# main.net
KiCad netlist of a schematic drawn in Altium Designer
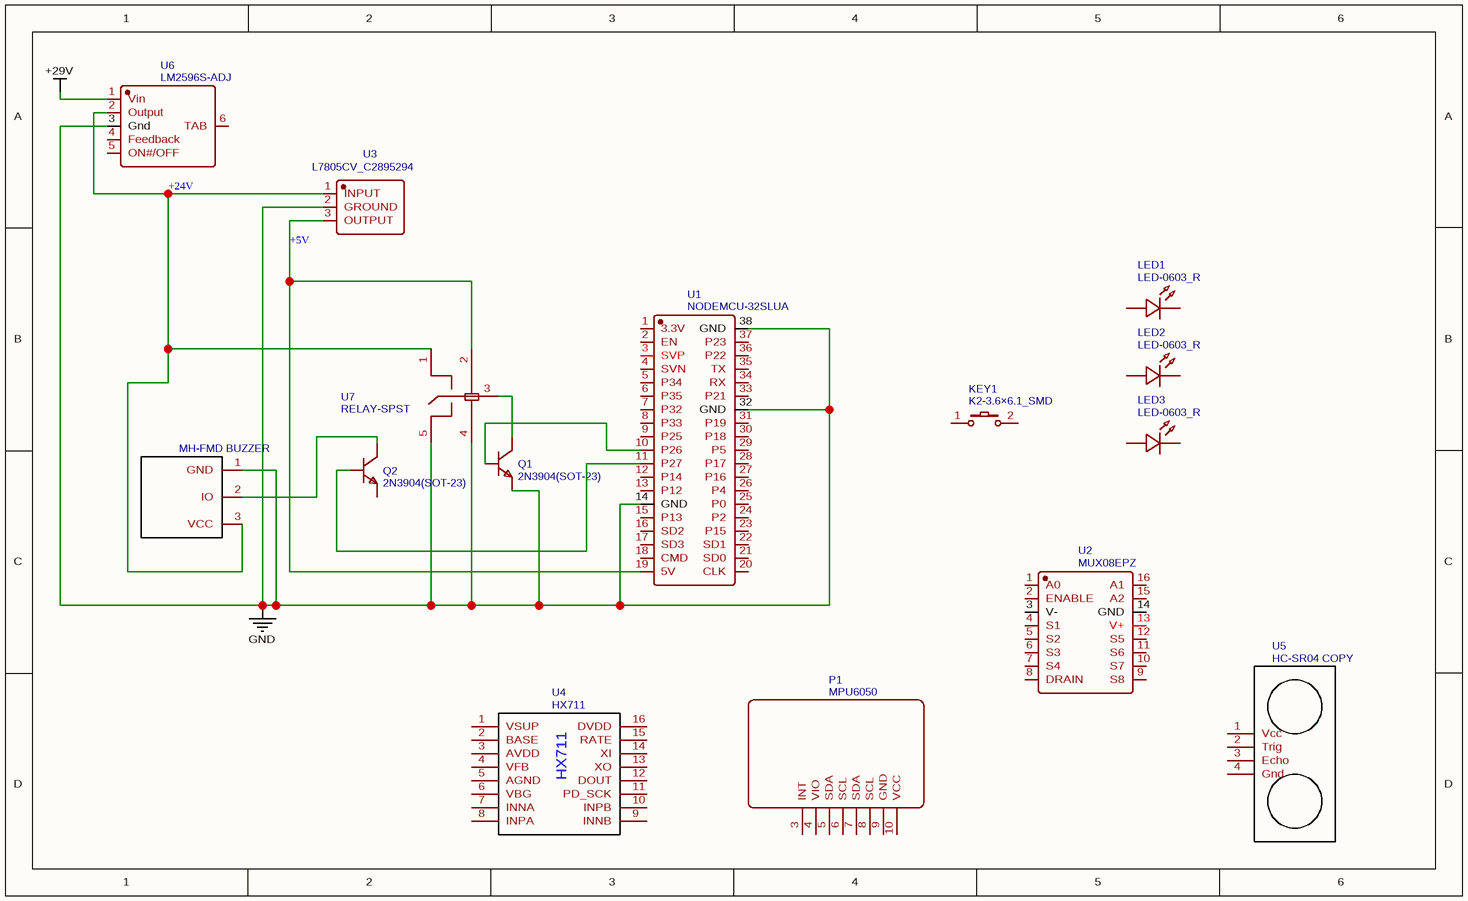
[diagram p0: main.schdoc]

(export (version "E")
  (design (tool "Eeschema 10.0.6"))
  (components
    (comp (ref "GND")
      (value "MH-FMD BUZZER")
      (fields (field (name "BOM_SUPPLIER PART") "MH-FMD") (field (name "CONTRIBUTOR") "toms56"))
      (libsource (lib "altium-import") (part "root_0_MH-FMD BUZZER_"))
    )
    (comp (ref "KEY1")
      (value "K2-3.6×6.1_SMD")
      (fields
        (field (name "BOM_SUPPLIER PART") "C118141")
        (field (name "BOM_MANUFACTURER PART") "K2-1107ST-A4SW-06")
        (field (name "CONTRIBUTOR") "LCEDA_Lib")
      )
      (libsource (lib "altium-import") (part "root_0_K2-3.6×6.1_SMD_"))
    )
    (comp (ref "LED1")
      (value "LED-0603_R")
      (fields
        (field (name "BOM_MANUFACTURER PART") "19-217/R6C-AL1M2VY/3T")
        (field (name "BOM_SUPPLIER PART") "C72044")
        (field (name "CONTRIBUTOR") "LCEDA_01")
      )
      (libsource (lib "altium-import") (part "root_0_LED-0603_R_"))
    )
    (comp (ref "LED2")
      (value "LED-0603_R")
      (fields
        (field (name "BOM_MANUFACTURER PART") "19-217/R6C-AL1M2VY/3T")
        (field (name "BOM_SUPPLIER PART") "C72044")
        (field (name "CONTRIBUTOR") "LCEDA_01")
      )
      (libsource (lib "altium-import") (part "root_0_LED-0603_R_"))
    )
    (comp (ref "LED3")
      (value "LED-0603_R")
      (fields
        (field (name "BOM_MANUFACTURER PART") "19-217/R6C-AL1M2VY/3T")
        (field (name "BOM_SUPPLIER PART") "C72044")
        (field (name "CONTRIBUTOR") "LCEDA_01")
      )
      (libsource (lib "altium-import") (part "root_0_LED-0603_R_"))
    )
    (comp (ref "P1")
      (value "MPU6050")
      (fields (field (name "CONTRIBUTOR") "AmrKhaled123"))
      (libsource (lib "altium-import") (part "root_0_MPU6050_"))
    )
    (comp (ref "Q1")
      (value "2N3904(SOT-23)")
      (fields
        (field (name "BOM_MANUFACTURER PART") "2n3904S-RTK/PS")
        (field (name "BOM_SUPPLIER PART") "C18536")
        (field (name "CONTRIBUTOR") "LCEDA_Lib")
      )
      (libsource (lib "altium-import") (part "root_0_2N3904(SOT-23)_"))
    )
    (comp (ref "Q2")
      (value "2N3904(SOT-23)")
      (fields
        (field (name "BOM_MANUFACTURER PART") "2n3904S-RTK/PS")
        (field (name "BOM_SUPPLIER PART") "C18536")
        (field (name "CONTRIBUTOR") "LCEDA_Lib")
      )
      (libsource (lib "altium-import") (part "root_0_2N3904(SOT-23)_"))
    )
    (comp (ref "U1")
      (value "NODEMCU-32SLUA")
      (fields
        (field (name "BOM_SUPPLIER PART") "C111436")
        (field (name "BOM_MANUFACTURER PART") "NodeMCU-32SLua")
        (field (name "CONTRIBUTOR") "lcsc")
      )
      (libsource (lib "altium-import") (part "root_0_NODEMCU-32SLUA_"))
    )
    (comp (ref "U2")
      (value "MUX08EPZ")
      (fields (field (name "BOM_SUPPLIER PART") "C690856") (field (name "CONTRIBUTOR") "LCSC"))
      (libsource (lib "altium-import") (part "root_0_MUX08EPZ_"))
    )
    (comp (ref "U3")
      (value "L7805CV_C2895294")
      (fields
        (field (name "BOM_SUPPLIER PART") "C2895294")
        (field (name "BOM_MANUFACTURER PART") "L7805CV带散热器")
        (field (name "CONTRIBUTOR") "LCSC")
      )
      (libsource (lib "altium-import") (part "root_0_L7805CV_C2895294_"))
    )
    (comp (ref "U4")
      (value "HX711")
      (fields (field (name "BOM_SUPPLIER PART") "C43656"))
      (libsource (lib "altium-import") (part "root_0_HX711_"))
    )
    (comp (ref "U5")
      (value "HC-SR04 COPY")
      (fields (field (name "CONTRIBUTOR") "allvex"))
      (libsource (lib "altium-import") (part "root_0_HC-SR04 COPY_"))
    )
    (comp (ref "U6")
      (value "LM2596S-ADJ")
      (fields (field (name "BOM_SUPPLIER PART") "C347423") (field (name "CONTRIBUTOR") "LCSC"))
      (libsource (lib "altium-import") (part "root_0_LM2596S-ADJ_"))
    )
    (comp (ref "U7")
      (value "RELAY-SPST")
      (fields
        (field (name "BOM_SUPPLIER PART") "C2941249")
        (field (name "BOM_MANUFACTURER PART") "Relay-SPST")
        (field (name "CONTRIBUTOR") "LCSC")
      )
      (libsource (lib "altium-import") (part "root_0_RELAY-SPST_"))
    )
  )
  (nets
    (net (code "1") (name "+29V") (class "Default")
      (node (ref "U6") (pin "1") (pinfunction "Vin_1") (pintype "passive"))
    )
    (net (code "2") (name "/+5V") (class "Default")
      (node (ref "U1") (pin "19") (pinfunction "5V_19") (pintype "passive"))
      (node (ref "U3") (pin "3") (pinfunction "OUTPUT_3") (pintype "passive"))
      (node (ref "U7") (pin "2") (pinfunction "2_2") (pintype "passive"))
    )
    (net (code "3") (name "/+24V") (class "Default")
      (node (ref "GND") (pin "3") (pinfunction "VCC_3") (pintype "passive"))
      (node (ref "U3") (pin "1") (pinfunction "INPUT_1") (pintype "passive"))
      (node (ref "U6") (pin "2") (pinfunction "Output_2") (pintype "passive"))
      (node (ref "U7") (pin "1") (pinfunction "1_1") (pintype "passive"))
    )
    (net (code "4") (name "GND") (class "Default")
      (node (ref "GND") (pin "1") (pinfunction "GND_1") (pintype "passive"))
      (node (ref "Q1") (pin "1") (pinfunction "E_1") (pintype "passive"))
      (node (ref "U1") (pin "14") (pinfunction "GND_14") (pintype "passive"))
      (node (ref "U1") (pin "32") (pinfunction "GND_32") (pintype "passive"))
      (node (ref "U1") (pin "38") (pinfunction "GND_38") (pintype "passive"))
      (node (ref "U3") (pin "2") (pinfunction "GROUND_2") (pintype "passive"))
      (node (ref "U6") (pin "3") (pinfunction "Gnd_3") (pintype "passive"))
      (node (ref "U7") (pin "4") (pinfunction "4_4") (pintype "passive"))
      (node (ref "U7") (pin "5") (pinfunction "5_5") (pintype "passive"))
    )
    (net (code "5") (name "Net-(GND-IO)") (class "Default")
      (node (ref "GND") (pin "2") (pinfunction "IO_2") (pintype "passive"))
      (node (ref "Q2") (pin "3") (pinfunction "C_3") (pintype "passive"))
    )
    (net (code "6") (name "Net-(Q1-B)") (class "Default")
      (node (ref "Q1") (pin "2") (pinfunction "B_2") (pintype "passive"))
      (node (ref "U1") (pin "10") (pinfunction "P26_10") (pintype "passive"))
    )
    (net (code "7") (name "Net-(Q1-C)") (class "Default")
      (node (ref "Q1") (pin "3") (pinfunction "C_3") (pintype "passive"))
      (node (ref "U7") (pin "3") (pinfunction "3_3") (pintype "passive"))
    )
    (net (code "8") (name "Net-(Q2-B)") (class "Default")
      (node (ref "Q2") (pin "2") (pinfunction "B_2") (pintype "passive"))
      (node (ref "U1") (pin "11") (pinfunction "P27_11") (pintype "passive"))
    )
    (net (code "9") (name "unconnected-(KEY1-Pad1)") (class "Default")
      (node (ref "KEY1") (pin "1") (pinfunction "1_1") (pintype "passive"))
    )
    (net (code "10") (name "unconnected-(KEY1-Pad2)") (class "Default")
      (node (ref "KEY1") (pin "2") (pinfunction "2_2") (pintype "passive"))
    )
    (net (code "11") (name "unconnected-(LED1-Pad1)") (class "Default")
      (node (ref "LED1") (pin "1") (pinfunction "1_1") (pintype "passive"))
    )
    (net (code "12") (name "unconnected-(LED1-Pad2)") (class "Default")
      (node (ref "LED1") (pin "2") (pinfunction "2_2") (pintype "passive"))
    )
    (net (code "13") (name "unconnected-(LED2-Pad1)") (class "Default")
      (node (ref "LED2") (pin "1") (pinfunction "1_1") (pintype "passive"))
    )
    (net (code "14") (name "unconnected-(LED2-Pad2)") (class "Default")
      (node (ref "LED2") (pin "2") (pinfunction "2_2") (pintype "passive"))
    )
    (net (code "15") (name "unconnected-(LED3-Pad1)") (class "Default")
      (node (ref "LED3") (pin "1") (pinfunction "1_1") (pintype "passive"))
    )
    (net (code "16") (name "unconnected-(LED3-Pad2)") (class "Default")
      (node (ref "LED3") (pin "2") (pinfunction "2_2") (pintype "passive"))
    )
    (net (code "17") (name "unconnected-(P1-GND-Pad9)") (class "Default")
      (node (ref "P1") (pin "9") (pinfunction "GND_9") (pintype "passive"))
    )
    (net (code "18") (name "unconnected-(P1-INT-Pad3)") (class "Default")
      (node (ref "P1") (pin "3") (pinfunction "INT_3") (pintype "passive"))
    )
    (net (code "19") (name "unconnected-(P1-SCL-Pad6)") (class "Default")
      (node (ref "P1") (pin "6") (pinfunction "SCL_6") (pintype "passive"))
    )
    (net (code "20") (name "unconnected-(P1-SCL-Pad8)") (class "Default")
      (node (ref "P1") (pin "8") (pinfunction "SCL_8") (pintype "passive"))
    )
    (net (code "21") (name "unconnected-(P1-SDA-Pad5)") (class "Default")
      (node (ref "P1") (pin "5") (pinfunction "SDA_5") (pintype "passive"))
    )
    (net (code "22") (name "unconnected-(P1-SDA-Pad7)") (class "Default")
      (node (ref "P1") (pin "7") (pinfunction "SDA_7") (pintype "passive"))
    )
    (net (code "23") (name "unconnected-(P1-VCC-Pad10)") (class "Default")
      (node (ref "P1") (pin "10") (pinfunction "VCC_10") (pintype "passive"))
    )
    (net (code "24") (name "unconnected-(P1-VIO-Pad4)") (class "Default")
      (node (ref "P1") (pin "4") (pinfunction "VIO_4") (pintype "passive"))
    )
    (net (code "25") (name "unconnected-(Q2-E-Pad1)") (class "Default")
      (node (ref "Q2") (pin "1") (pinfunction "E_1") (pintype "passive"))
    )
    (net (code "26") (name "unconnected-(U1-3.3V-Pad1)") (class "Default")
      (node (ref "U1") (pin "1") (pinfunction "3.3V_1") (pintype "passive"))
    )
    (net (code "27") (name "unconnected-(U1-CLK-Pad20)") (class "Default")
      (node (ref "U1") (pin "20") (pinfunction "CLK_20") (pintype "passive"))
    )
    (net (code "28") (name "unconnected-(U1-CMD-Pad18)") (class "Default")
      (node (ref "U1") (pin "18") (pinfunction "CMD_18") (pintype "passive"))
    )
    (net (code "29") (name "unconnected-(U1-EN-Pad2)") (class "Default")
      (node (ref "U1") (pin "2") (pinfunction "EN_2") (pintype "passive"))
    )
    (net (code "30") (name "unconnected-(U1-P0-Pad25)") (class "Default")
      (node (ref "U1") (pin "25") (pinfunction "P0_25") (pintype "passive"))
    )
    (net (code "31") (name "unconnected-(U1-P2-Pad24)") (class "Default")
      (node (ref "U1") (pin "24") (pinfunction "P2_24") (pintype "passive"))
    )
    (net (code "32") (name "unconnected-(U1-P4-Pad26)") (class "Default")
      (node (ref "U1") (pin "26") (pinfunction "P4_26") (pintype "passive"))
    )
    (net (code "33") (name "unconnected-(U1-P5-Pad29)") (class "Default")
      (node (ref "U1") (pin "29") (pinfunction "P5_29") (pintype "passive"))
    )
    (net (code "34") (name "unconnected-(U1-P12-Pad13)") (class "Default")
      (node (ref "U1") (pin "13") (pinfunction "P12_13") (pintype "passive"))
    )
    (net (code "35") (name "unconnected-(U1-P13-Pad15)") (class "Default")
      (node (ref "U1") (pin "15") (pinfunction "P13_15") (pintype "passive"))
    )
    (net (code "36") (name "unconnected-(U1-P14-Pad12)") (class "Default")
      (node (ref "U1") (pin "12") (pinfunction "P14_12") (pintype "passive"))
    )
    (net (code "37") (name "unconnected-(U1-P15-Pad23)") (class "Default")
      (node (ref "U1") (pin "23") (pinfunction "P15_23") (pintype "passive"))
    )
    (net (code "38") (name "unconnected-(U1-P16-Pad27)") (class "Default")
      (node (ref "U1") (pin "27") (pinfunction "P16_27") (pintype "passive"))
    )
    (net (code "39") (name "unconnected-(U1-P17-Pad28)") (class "Default")
      (node (ref "U1") (pin "28") (pinfunction "P17_28") (pintype "passive"))
    )
    (net (code "40") (name "unconnected-(U1-P18-Pad30)") (class "Default")
      (node (ref "U1") (pin "30") (pinfunction "P18_30") (pintype "passive"))
    )
    (net (code "41") (name "unconnected-(U1-P19-Pad31)") (class "Default")
      (node (ref "U1") (pin "31") (pinfunction "P19_31") (pintype "passive"))
    )
    (net (code "42") (name "unconnected-(U1-P21-Pad33)") (class "Default")
      (node (ref "U1") (pin "33") (pinfunction "P21_33") (pintype "passive"))
    )
    (net (code "43") (name "unconnected-(U1-P22-Pad36)") (class "Default")
      (node (ref "U1") (pin "36") (pinfunction "P22_36") (pintype "passive"))
    )
    (net (code "44") (name "unconnected-(U1-P23-Pad37)") (class "Default")
      (node (ref "U1") (pin "37") (pinfunction "P23_37") (pintype "passive"))
    )
    (net (code "45") (name "unconnected-(U1-P25-Pad9)") (class "Default")
      (node (ref "U1") (pin "9") (pinfunction "P25_9") (pintype "passive"))
    )
    (net (code "46") (name "unconnected-(U1-P32-Pad7)") (class "Default")
      (node (ref "U1") (pin "7") (pinfunction "P32_7") (pintype "passive"))
    )
    (net (code "47") (name "unconnected-(U1-P33-Pad8)") (class "Default")
      (node (ref "U1") (pin "8") (pinfunction "P33_8") (pintype "passive"))
    )
    (net (code "48") (name "unconnected-(U1-P34-Pad5)") (class "Default")
      (node (ref "U1") (pin "5") (pinfunction "P34_5") (pintype "passive"))
    )
    (net (code "49") (name "unconnected-(U1-P35-Pad6)") (class "Default")
      (node (ref "U1") (pin "6") (pinfunction "P35_6") (pintype "passive"))
    )
    (net (code "50") (name "unconnected-(U1-RX-Pad34)") (class "Default")
      (node (ref "U1") (pin "34") (pinfunction "RX_34") (pintype "passive"))
    )
    (net (code "51") (name "unconnected-(U1-SD0-Pad21)") (class "Default")
      (node (ref "U1") (pin "21") (pinfunction "SD0_21") (pintype "passive"))
    )
    (net (code "52") (name "unconnected-(U1-SD1-Pad22)") (class "Default")
      (node (ref "U1") (pin "22") (pinfunction "SD1_22") (pintype "passive"))
    )
    (net (code "53") (name "unconnected-(U1-SD2-Pad16)") (class "Default")
      (node (ref "U1") (pin "16") (pinfunction "SD2_16") (pintype "passive"))
    )
    (net (code "54") (name "unconnected-(U1-SD3-Pad17)") (class "Default")
      (node (ref "U1") (pin "17") (pinfunction "SD3_17") (pintype "passive"))
    )
    (net (code "55") (name "unconnected-(U1-SVN-Pad4)") (class "Default")
      (node (ref "U1") (pin "4") (pinfunction "SVN_4") (pintype "passive"))
    )
    (net (code "56") (name "unconnected-(U1-SVP-Pad3)") (class "Default")
      (node (ref "U1") (pin "3") (pinfunction "SVP_3") (pintype "passive"))
    )
    (net (code "57") (name "unconnected-(U1-TX-Pad35)") (class "Default")
      (node (ref "U1") (pin "35") (pinfunction "TX_35") (pintype "passive"))
    )
    (net (code "58") (name "unconnected-(U2-A0-Pad1)") (class "Default")
      (node (ref "U2") (pin "1") (pinfunction "A0_1") (pintype "passive"))
    )
    (net (code "59") (name "unconnected-(U2-A1-Pad16)") (class "Default")
      (node (ref "U2") (pin "16") (pinfunction "A1_16") (pintype "passive"))
    )
    (net (code "60") (name "unconnected-(U2-A2-Pad15)") (class "Default")
      (node (ref "U2") (pin "15") (pinfunction "A2_15") (pintype "passive"))
    )
    (net (code "61") (name "unconnected-(U2-DRAIN-Pad8)") (class "Default")
      (node (ref "U2") (pin "8") (pinfunction "DRAIN_8") (pintype "passive"))
    )
    (net (code "62") (name "unconnected-(U2-ENABLE-Pad2)") (class "Default")
      (node (ref "U2") (pin "2") (pinfunction "ENABLE_2") (pintype "passive"))
    )
    (net (code "63") (name "unconnected-(U2-GND-Pad14)") (class "Default")
      (node (ref "U2") (pin "14") (pinfunction "GND_14") (pintype "passive"))
    )
    (net (code "64") (name "unconnected-(U2-S1-Pad4)") (class "Default")
      (node (ref "U2") (pin "4") (pinfunction "S1_4") (pintype "passive"))
    )
    (net (code "65") (name "unconnected-(U2-S2-Pad5)") (class "Default")
      (node (ref "U2") (pin "5") (pinfunction "S2_5") (pintype "passive"))
    )
    (net (code "66") (name "unconnected-(U2-S3-Pad6)") (class "Default")
      (node (ref "U2") (pin "6") (pinfunction "S3_6") (pintype "passive"))
    )
    (net (code "67") (name "unconnected-(U2-S4-Pad7)") (class "Default")
      (node (ref "U2") (pin "7") (pinfunction "S4_7") (pintype "passive"))
    )
    (net (code "68") (name "unconnected-(U2-S5-Pad12)") (class "Default")
      (node (ref "U2") (pin "12") (pinfunction "S5_12") (pintype "passive"))
    )
    (net (code "69") (name "unconnected-(U2-S6-Pad11)") (class "Default")
      (node (ref "U2") (pin "11") (pinfunction "S6_11") (pintype "passive"))
    )
    (net (code "70") (name "unconnected-(U2-S7-Pad10)") (class "Default")
      (node (ref "U2") (pin "10") (pinfunction "S7_10") (pintype "passive"))
    )
    (net (code "71") (name "unconnected-(U2-S8-Pad9)") (class "Default")
      (node (ref "U2") (pin "9") (pinfunction "S8_9") (pintype "passive"))
    )
    (net (code "72") (name "unconnected-(U2-V+-Pad13)") (class "Default")
      (node (ref "U2") (pin "13") (pinfunction "V+_13") (pintype "passive"))
    )
    (net (code "73") (name "unconnected-(U2-V--Pad3)") (class "Default")
      (node (ref "U2") (pin "3") (pinfunction "V-_3") (pintype "passive"))
    )
    (net (code "74") (name "unconnected-(U4-AGND-Pad5)") (class "Default")
      (node (ref "U4") (pin "5") (pinfunction "AGND_5") (pintype "passive"))
    )
    (net (code "75") (name "unconnected-(U4-AVDD-Pad3)") (class "Default")
      (node (ref "U4") (pin "3") (pinfunction "AVDD_3") (pintype "passive"))
    )
    (net (code "76") (name "unconnected-(U4-BASE-Pad2)") (class "Default")
      (node (ref "U4") (pin "2") (pinfunction "BASE_2") (pintype "passive"))
    )
    (net (code "77") (name "unconnected-(U4-DOUT-Pad12)") (class "Default")
      (node (ref "U4") (pin "12") (pinfunction "DOUT_12") (pintype "passive"))
    )
    (net (code "78") (name "unconnected-(U4-DVDD-Pad16)") (class "Default")
      (node (ref "U4") (pin "16") (pinfunction "DVDD_16") (pintype "passive"))
    )
    (net (code "79") (name "unconnected-(U4-INNA-Pad7)") (class "Default")
      (node (ref "U4") (pin "7") (pinfunction "INNA_7") (pintype "passive"))
    )
    (net (code "80") (name "unconnected-(U4-INNB-Pad9)") (class "Default")
      (node (ref "U4") (pin "9") (pinfunction "INNB_9") (pintype "passive"))
    )
    (net (code "81") (name "unconnected-(U4-INPA-Pad8)") (class "Default")
      (node (ref "U4") (pin "8") (pinfunction "INPA_8") (pintype "passive"))
    )
    (net (code "82") (name "unconnected-(U4-INPB-Pad10)") (class "Default")
      (node (ref "U4") (pin "10") (pinfunction "INPB_10") (pintype "passive"))
    )
    (net (code "83") (name "unconnected-(U4-PD_SCK-Pad11)") (class "Default")
      (node (ref "U4") (pin "11") (pinfunction "PD_SCK_11") (pintype "passive"))
    )
    (net (code "84") (name "unconnected-(U4-RATE-Pad15)") (class "Default")
      (node (ref "U4") (pin "15") (pinfunction "RATE_15") (pintype "passive"))
    )
    (net (code "85") (name "unconnected-(U4-VBG-Pad6)") (class "Default")
      (node (ref "U4") (pin "6") (pinfunction "VBG_6") (pintype "passive"))
    )
    (net (code "86") (name "unconnected-(U4-VFB-Pad4)") (class "Default")
      (node (ref "U4") (pin "4") (pinfunction "VFB_4") (pintype "passive"))
    )
    (net (code "87") (name "unconnected-(U4-VSUP-Pad1)") (class "Default")
      (node (ref "U4") (pin "1") (pinfunction "VSUP_1") (pintype "passive"))
    )
    (net (code "88") (name "unconnected-(U4-XI-Pad14)") (class "Default")
      (node (ref "U4") (pin "14") (pinfunction "XI_14") (pintype "passive"))
    )
    (net (code "89") (name "unconnected-(U4-XO-Pad13)") (class "Default")
      (node (ref "U4") (pin "13") (pinfunction "XO_13") (pintype "passive"))
    )
    (net (code "90") (name "unconnected-(U5-Echo-Pad3)") (class "Default")
      (node (ref "U5") (pin "3") (pinfunction "Echo_3") (pintype "passive"))
    )
    (net (code "91") (name "unconnected-(U5-Gnd-Pad4)") (class "Default")
      (node (ref "U5") (pin "4") (pinfunction "Gnd_4") (pintype "passive"))
    )
    (net (code "92") (name "unconnected-(U5-Trig-Pad2)") (class "Default")
      (node (ref "U5") (pin "2") (pinfunction "Trig_2") (pintype "passive"))
    )
    (net (code "93") (name "unconnected-(U5-Vcc-Pad1)") (class "Default")
      (node (ref "U5") (pin "1") (pinfunction "Vcc_1") (pintype "passive"))
    )
    (net (code "94") (name "unconnected-(U6-Feedback-Pad4)") (class "Default")
      (node (ref "U6") (pin "4") (pinfunction "Feedback_4") (pintype "passive"))
    )
    (net (code "95") (name "unconnected-(U6-ON#{slash}OFF-Pad5)") (class "Default")
      (node (ref "U6") (pin "5") (pinfunction "ON#/OFF_5") (pintype "passive"))
    )
    (net (code "96") (name "unconnected-(U6-TAB-Pad6)") (class "Default")
      (node (ref "U6") (pin "6") (pinfunction "TAB_6") (pintype "passive"))
    )
  )
)
